# ST_LINK_V2_1.net
KiCad netlist of a schematic drawn in Altium Designer
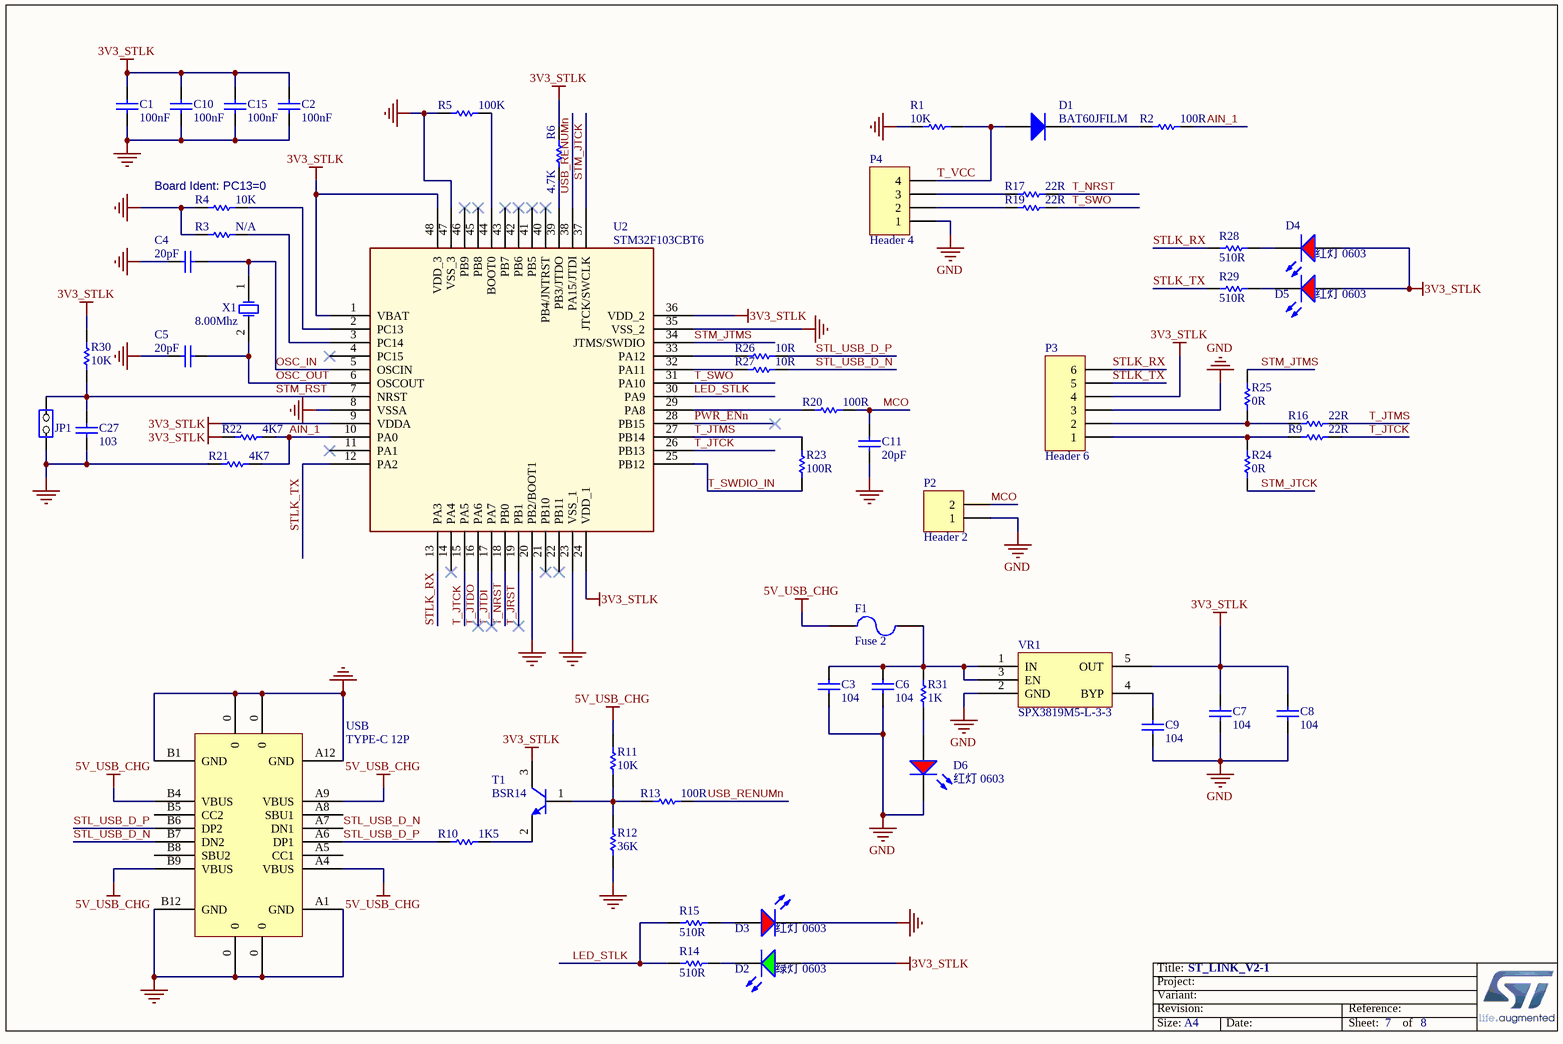
[diagram p0: ST_LINK_V2.1.SchDoc]

(export (version "E")
  (design (tool "Eeschema 10.0.6"))
  (components
    (comp (ref "C1")
      (value "100nF")
      (footprint "0603_C")
      (description "Capacitor, MLCC, 100nF, 16V, X7R, 10%, 0603, T=0,8mm")
      (fields
        (field (name "INTERNAL_PART_NUMBER") "MCD-00211")
        (field (name "MANUFACTURER_PART_NUMBER") "CC0603KRX7R7BB104")
        (field (name "PROVIDED_BY") "Subcon")
      )
      (libsource (lib "MCD_PARTS_database") (part "Capacitor"))
    )
    (comp (ref "C2")
      (value "100nF")
      (footprint "0603_C")
      (description "Capacitor, MLCC, 100nF, 16V, X7R, 10%, 0603, T=0,8mm")
      (fields
        (field (name "INTERNAL_PART_NUMBER") "MCD-00211")
        (field (name "MANUFACTURER_PART_NUMBER") "CC0603KRX7R7BB104")
        (field (name "PROVIDED_BY") "Subcon")
      )
      (libsource (lib "MCD_PARTS_database") (part "Capacitor"))
    )
    (comp (ref "C3")
      (value "104")
      (footprint "0603_C")
      (description "贴片电容")
      (libsource (lib "Miscellaneous Devices LC") (part "0603 2.7pF (2R7) 0.25pF 50V"))
    )
    (comp (ref "C4")
      (value "20pF")
      (footprint "0603_C")
      (description "Capacitor, MLCC, 10pF, 50V, NPO, 5%, 0603, T=0,8mm")
      (fields
        (field (name "INTERNAL_PART_NUMBER") "MCD-00637")
        (field (name "MANUFACTURER_PART_NUMBER") "CC0603JRNPO9BN100")
        (field (name "PROVIDED_BY") "subcon")
      )
      (libsource (lib "MCD_PARTS_database") (part "Capacitor"))
    )
    (comp (ref "C5")
      (value "20pF")
      (footprint "0603_C")
      (description "Capacitor, MLCC, 10pF, 50V, NPO, 5%, 0603, T=0,8mm")
      (fields
        (field (name "INTERNAL_PART_NUMBER") "MCD-00637")
        (field (name "MANUFACTURER_PART_NUMBER") "CC0603JRNPO9BN100")
        (field (name "PROVIDED_BY") "subcon")
      )
      (libsource (lib "MCD_PARTS_database") (part "Capacitor"))
    )
    (comp (ref "C6")
      (value "104")
      (footprint "0603_C")
      (description "贴片电容")
      (libsource (lib "Miscellaneous Devices LC") (part "0603 2.7pF (2R7) 0.25pF 50V"))
    )
    (comp (ref "C7")
      (value "104")
      (footprint "0603_C")
      (description "贴片电容")
      (libsource (lib "Miscellaneous Devices LC") (part "0603 2.7pF (2R7) 0.25pF 50V"))
    )
    (comp (ref "C8")
      (value "104")
      (footprint "0603_C")
      (description "贴片电容")
      (libsource (lib "Miscellaneous Devices LC") (part "0603 2.7pF (2R7) 0.25pF 50V"))
    )
    (comp (ref "C9")
      (value "104")
      (footprint "0603_C")
      (description "贴片电容")
      (libsource (lib "Miscellaneous Devices LC") (part "0603 2.7pF (2R7) 0.25pF 50V"))
    )
    (comp (ref "C10")
      (value "100nF")
      (footprint "0603_C")
      (description "Capacitor, MLCC, 100nF, 16V, X7R, 10%, 0603, T=0,8mm")
      (fields
        (field (name "INTERNAL_PART_NUMBER") "MCD-00211")
        (field (name "MANUFACTURER_PART_NUMBER") "CC0603KRX7R7BB104")
        (field (name "PROVIDED_BY") "Subcon")
      )
      (libsource (lib "MCD_PARTS_database") (part "Capacitor"))
    )
    (comp (ref "C11")
      (value "20pF")
      (footprint "0603_C")
      (description "Capacitor, MLCC, 20pF, 50V, NPO, 5%, 0603, T=0,8mm")
      (fields
        (field (name "INTERNAL_PART_NUMBER") "MCD-00638")
        (field (name "MANUFACTURER_PART_NUMBER") "CC0603JRNPO9BN200")
        (field (name "PROVIDED_BY") "Subcon")
      )
      (libsource (lib "MCD_PARTS_database") (part "Capacitor"))
    )
    (comp (ref "C15")
      (value "100nF")
      (footprint "0603_C")
      (description "Capacitor, MLCC, 100nF, 16V, X7R, 10%, 0603, T=0,8mm")
      (fields
        (field (name "INTERNAL_PART_NUMBER") "MCD-00211")
        (field (name "MANUFACTURER_PART_NUMBER") "CC0603KRX7R7BB104")
        (field (name "PROVIDED_BY") "Subcon")
      )
      (libsource (lib "MCD_PARTS_database") (part "Capacitor"))
    )
    (comp (ref "C27")
      (value "103")
      (footprint "0603_C")
      (description "Capacitor, MLCC, 100nF, 16V, X7R, 10%, 0603, T=0,8mm")
      (fields
        (field (name "INTERNAL_PART_NUMBER") "MCD-00211")
        (field (name "MANUFACTURER_PART_NUMBER") "CC0603KRX7R7BB104")
        (field (name "PROVIDED_BY") "Subcon")
      )
      (libsource (lib "MCD_PARTS_database") (part "Capacitor"))
    )
    (comp (ref "D1")
      (value "BAT60JFILM")
      (footprint "SOD-323")
      (fields
        (field (name "INTERNAL_PART_NUMBER") "MCD-00034")
        (field (name "MANUFACTURER") "STMICROELECTRONICS")
        (field (name "PROVIDED_BY") "Subcon")
      )
      (libsource (lib "MCD_PARTS_database") (part "BAT60JFILM"))
    )
    (comp (ref "D2")
      (value "绿灯 0603")
      (footprint "0603_LED_S1")
      (description "发光二极管")
      (libsource (lib "Miscellaneous Devices LC") (part "0603 绿灯"))
    )
    (comp (ref "D3")
      (value "红灯 0603")
      (footprint "0603_LED_S1")
      (description "发光二极管")
      (libsource (lib "Miscellaneous Devices LC") (part "0603 红灯"))
    )
    (comp (ref "D4")
      (value "红灯 0603")
      (footprint "0603_LED_S1")
      (description "发光二极管")
      (libsource (lib "Miscellaneous Devices LC") (part "0603 红灯"))
    )
    (comp (ref "D5")
      (value "红灯 0603")
      (footprint "0603_LED_S1")
      (description "发光二极管")
      (libsource (lib "Miscellaneous Devices LC") (part "0603 红灯"))
    )
    (comp (ref "D6")
      (value "红灯 0603")
      (footprint "0603_LED_S1")
      (description "发光二极管")
      (libsource (lib "Miscellaneous Devices LC") (part "0603 红灯"))
    )
    (comp (ref "F1")
      (value "Fuse 2")
      (footprint "1206_R")
      (description "Fuse")
      (fields (field (name "PUBLISHER") "Altium Limited"))
      (libsource (lib "Miscellaneous Devices") (part "Fuse 2"))
    )
    (comp (ref "JP1")
      (value "Jumper Header 2x1")
      (footprint "HDR1X2")
      (description "Header, 2x1, 2,54mm, VR, TH, Height 5.84mm/2.54mm")
      (fields
        (field (name "INTERNAL_PART_NUMBER") "MCD-00045")
        (field (name "MANUFACTURER_PART_NUMBER") "TSW-102-07-x-S")
        (field (name "PROVIDED_BY") "Subcon")
      )
      (libsource (lib "MCD_PARTS_database") (part "Jumper Header 2x1"))
    )
    (comp (ref "P2")
      (value "Header 2")
      (footprint "HDR1X2")
      (description "Header, 2-Pin")
      (fields (field (name "PUBLISHER") "Altium Limited"))
      (libsource (lib "Miscellaneous Connectors") (part "Header 2"))
    )
    (comp (ref "P3")
      (value "Header 6")
      (footprint "HDR1X6")
      (description "Header, 6-Pin")
      (fields (field (name "PUBLISHER") "Altium Limited"))
      (libsource (lib "Miscellaneous Connectors") (part "Header 6"))
    )
    (comp (ref "P4")
      (value "Header 4")
      (footprint "HDR1X4")
      (description "Header, 4-Pin")
      (fields (field (name "PUBLISHER") "Altium Limited"))
      (libsource (lib "Miscellaneous Connectors") (part "Header 4"))
    )
    (comp (ref "R1")
      (value "10K")
      (footprint "0603_R")
      (description "Resistor,10K,0603,1%,1/10W")
      (fields
        (field (name "INTERNAL_PART_NUMBER") "MCD-00220")
        (field (name "MANUFACTURER_PART_NUMBER") "RC0603FR-0710KL")
        (field (name "PROVIDED_BY") "Subcon")
      )
      (libsource (lib "MCD_PARTS_database") (part "Resistor"))
    )
    (comp (ref "R2")
      (value "100R")
      (footprint "0603_R")
      (description "Resistor,22R,0603,1%,1/10W")
      (fields
        (field (name "INTERNAL_PART_NUMBER") "MCD-00066")
        (field (name "MANUFACTURER_PART_NUMBER") "RC0603FR-0722RL")
        (field (name "PROVIDED_BY") "Subcon")
      )
      (libsource (lib "MCD_PARTS_database") (part "Resistor"))
    )
    (comp (ref "R3")
      (value "N/A")
      (footprint "0603_R")
      (description "Resistor,10K,0603,1%,1/10W")
      (fields
        (field (name "INTERNAL_PART_NUMBER") "MCD-00220")
        (field (name "MANUFACTURER_PART_NUMBER") "RC0603FR-0710KL")
        (field (name "PROVIDED_BY") "Subcon")
      )
      (libsource (lib "MCD_PARTS_database") (part "Resistor"))
    )
    (comp (ref "R4")
      (value "10K")
      (footprint "0603_R")
      (description "Resistor,10K,0603,1%,1/10W")
      (fields
        (field (name "INTERNAL_PART_NUMBER") "MCD-00220")
        (field (name "MANUFACTURER_PART_NUMBER") "RC0603FR-0710KL")
        (field (name "PROVIDED_BY") "Subcon")
      )
      (libsource (lib "MCD_PARTS_database") (part "Resistor"))
    )
    (comp (ref "R5")
      (value "100K")
      (footprint "0603_R")
      (description "Resistor,100K,0603,1%,1/10W")
      (fields
        (field (name "INTERNAL_PART_NUMBER") "MCD-00223")
        (field (name "MANUFACTURER_PART_NUMBER") "RC0603FR-07100KL")
        (field (name "PROVIDED_BY") "Subcon")
      )
      (libsource (lib "MCD_PARTS_database") (part "Resistor"))
    )
    (comp (ref "R6")
      (value "4.7K")
      (footprint "0603_R")
      (description "Resistor,330R,0603,1%,1/10W")
      (fields
        (field (name "INTERNAL_PART_NUMBER") "MCD-00197")
        (field (name "MANUFACTURER_PART_NUMBER") "RC0603FR-07330RL")
        (field (name "PROVIDED_BY") "Subcon")
      )
      (libsource (lib "MCD_PARTS_database") (part "Resistor"))
    )
    (comp (ref "R9")
      (value "22R")
      (footprint "0603_R")
      (description "Resistor,22R,0603,1%,1/10W")
      (fields
        (field (name "INTERNAL_PART_NUMBER") "MCD-00066")
        (field (name "MANUFACTURER_PART_NUMBER") "RC0603FR-0722RL")
        (field (name "PROVIDED_BY") "Subcon")
      )
      (libsource (lib "MCD_PARTS_database") (part "Resistor"))
    )
    (comp (ref "R10")
      (value "1K5")
      (footprint "0603_R")
      (description "Resistor,1K5,0603,1%,1/10W")
      (fields
        (field (name "INTERNAL_PART_NUMBER") "MCD-00217")
        (field (name "MANUFACTURER_PART_NUMBER") "RC0603FR-071K5L")
        (field (name "PROVIDED_BY") "Subcon")
      )
      (libsource (lib "MCD_PARTS_database") (part "Resistor"))
    )
    (comp (ref "R11")
      (value "10K")
      (footprint "0603_R")
      (description "Resistor,10K,0603,1%,1/10W")
      (fields
        (field (name "INTERNAL_PART_NUMBER") "MCD-00220")
        (field (name "MANUFACTURER_PART_NUMBER") "RC0603FR-0710KL")
        (field (name "PROVIDED_BY") "Subcon")
      )
      (libsource (lib "MCD_PARTS_database") (part "Resistor"))
    )
    (comp (ref "R12")
      (value "36K")
      (footprint "0603_R")
      (description "Resistor,36K,0603,1%,1/10W")
      (fields
        (field (name "INTERNAL_PART_NUMBER") "MCD-00221")
        (field (name "MANUFACTURER_PART_NUMBER") "RC0603FR-0736KL")
        (field (name "PROVIDED_BY") "Subcon")
      )
      (libsource (lib "MCD_PARTS_database") (part "Resistor"))
    )
    (comp (ref "R13")
      (value "100R")
      (footprint "0603_R")
      (description "Resistor,100R,0603,1%,1/10W")
      (fields
        (field (name "INTERNAL_PART_NUMBER") "MCD-00224")
        (field (name "MANUFACTURER_PART_NUMBER") "RC0603FR-07100RL")
        (field (name "PROVIDED_BY") "Subcon")
      )
      (libsource (lib "MCD_PARTS_database") (part "Resistor"))
    )
    (comp (ref "R14")
      (value "510R")
      (footprint "0603_R")
      (description "Resistor,330R,0603,1%,1/10W")
      (fields
        (field (name "INTERNAL_PART_NUMBER") "MCD-00197")
        (field (name "MANUFACTURER_PART_NUMBER") "RC0603FR-07330RL")
        (field (name "PROVIDED_BY") "Subcon")
      )
      (libsource (lib "MCD_PARTS_database") (part "Resistor"))
    )
    (comp (ref "R15")
      (value "510R")
      (footprint "0603_R")
      (description "Resistor,330R,0603,1%,1/10W")
      (fields
        (field (name "INTERNAL_PART_NUMBER") "MCD-00197")
        (field (name "MANUFACTURER_PART_NUMBER") "RC0603FR-07330RL")
        (field (name "PROVIDED_BY") "Subcon")
      )
      (libsource (lib "MCD_PARTS_database") (part "Resistor"))
    )
    (comp (ref "R16")
      (value "22R")
      (footprint "0603_R")
      (description "Resistor,22R,0603,1%,1/10W")
      (fields
        (field (name "INTERNAL_PART_NUMBER") "MCD-00066")
        (field (name "MANUFACTURER_PART_NUMBER") "RC0603FR-0722RL")
        (field (name "PROVIDED_BY") "Subcon")
      )
      (libsource (lib "MCD_PARTS_database") (part "Resistor"))
    )
    (comp (ref "R17")
      (value "22R")
      (footprint "0603_R")
      (description "Resistor,22R,0603,1%,1/10W")
      (fields
        (field (name "INTERNAL_PART_NUMBER") "MCD-00066")
        (field (name "MANUFACTURER_PART_NUMBER") "RC0603FR-0722RL")
        (field (name "PROVIDED_BY") "Subcon")
      )
      (libsource (lib "MCD_PARTS_database") (part "Resistor"))
    )
    (comp (ref "R19")
      (value "22R")
      (footprint "0603_R")
      (description "Resistor,22R,0603,1%,1/10W")
      (fields
        (field (name "INTERNAL_PART_NUMBER") "MCD-00066")
        (field (name "MANUFACTURER_PART_NUMBER") "RC0603FR-0722RL")
        (field (name "PROVIDED_BY") "Subcon")
      )
      (libsource (lib "MCD_PARTS_database") (part "Resistor"))
    )
    (comp (ref "R20")
      (value "100R")
      (footprint "0603_R")
      (description "Resistor,100R,0603,1%,1/10W")
      (fields
        (field (name "INTERNAL_PART_NUMBER") "MCD-00224")
        (field (name "MANUFACTURER_PART_NUMBER") "RC0603FR-07100RL")
        (field (name "PROVIDED_BY") "Subcon")
      )
      (libsource (lib "MCD_PARTS_database") (part "Resistor"))
    )
    (comp (ref "R21")
      (value "4K7")
      (footprint "0603_R")
      (description "Resistor,4K7,0603,1%,1/10W")
      (fields
        (field (name "INTERNAL_PART_NUMBER") "MCD-00219")
        (field (name "MANUFACTURER_PART_NUMBER") "RC0603FR-074K7L")
        (field (name "PROVIDED_BY") "Subcon")
      )
      (libsource (lib "MCD_PARTS_database") (part "Resistor"))
    )
    (comp (ref "R22")
      (value "4K7")
      (footprint "0603_R")
      (description "Resistor,4K7,0603,1%,1/10W")
      (fields
        (field (name "INTERNAL_PART_NUMBER") "MCD-00219")
        (field (name "MANUFACTURER_PART_NUMBER") "RC0603FR-074K7L")
        (field (name "PROVIDED_BY") "Subcon")
      )
      (libsource (lib "MCD_PARTS_database") (part "Resistor"))
    )
    (comp (ref "R23")
      (value "100R")
      (footprint "0603_R")
      (description "Resistor,100R,0603,1%,1/10W")
      (fields
        (field (name "INTERNAL_PART_NUMBER") "MCD-00224")
        (field (name "MANUFACTURER_PART_NUMBER") "RC0603FR-07100RL")
        (field (name "PROVIDED_BY") "Subcon")
      )
      (libsource (lib "MCD_PARTS_database") (part "Resistor"))
    )
    (comp (ref "R24")
      (value "0R")
      (footprint "0603_R")
      (description "Resistor,22R,0603,1%,1/10W")
      (fields
        (field (name "INTERNAL_PART_NUMBER") "MCD-00066")
        (field (name "MANUFACTURER_PART_NUMBER") "RC0603FR-0722RL")
        (field (name "PROVIDED_BY") "Subcon")
      )
      (libsource (lib "MCD_PARTS_database") (part "Resistor"))
    )
    (comp (ref "R25")
      (value "0R")
      (footprint "0603_R")
      (description "Resistor,22R,0603,1%,1/10W")
      (fields
        (field (name "INTERNAL_PART_NUMBER") "MCD-00066")
        (field (name "MANUFACTURER_PART_NUMBER") "RC0603FR-0722RL")
        (field (name "PROVIDED_BY") "Subcon")
      )
      (libsource (lib "MCD_PARTS_database") (part "Resistor"))
    )
    (comp (ref "R26")
      (value "10R")
      (footprint "0603_R")
      (description "Resistor,100R,0603,1%,1/10W")
      (fields
        (field (name "INTERNAL_PART_NUMBER") "MCD-00224")
        (field (name "MANUFACTURER_PART_NUMBER") "RC0603FR-07100RL")
        (field (name "PROVIDED_BY") "Subcon")
      )
      (libsource (lib "MCD_PARTS_database") (part "Resistor"))
    )
    (comp (ref "R27")
      (value "10R")
      (footprint "0603_R")
      (description "Resistor,100R,0603,1%,1/10W")
      (fields
        (field (name "INTERNAL_PART_NUMBER") "MCD-00224")
        (field (name "MANUFACTURER_PART_NUMBER") "RC0603FR-07100RL")
        (field (name "PROVIDED_BY") "Subcon")
      )
      (libsource (lib "MCD_PARTS_database") (part "Resistor"))
    )
    (comp (ref "R28")
      (value "510R")
      (footprint "0603_R")
      (description "Resistor,330R,0603,1%,1/10W")
      (fields
        (field (name "INTERNAL_PART_NUMBER") "MCD-00197")
        (field (name "MANUFACTURER_PART_NUMBER") "RC0603FR-07330RL")
        (field (name "PROVIDED_BY") "Subcon")
      )
      (libsource (lib "MCD_PARTS_database") (part "Resistor"))
    )
    (comp (ref "R29")
      (value "510R")
      (footprint "0603_R")
      (description "Resistor,330R,0603,1%,1/10W")
      (fields
        (field (name "INTERNAL_PART_NUMBER") "MCD-00197")
        (field (name "MANUFACTURER_PART_NUMBER") "RC0603FR-07330RL")
        (field (name "PROVIDED_BY") "Subcon")
      )
      (libsource (lib "MCD_PARTS_database") (part "Resistor"))
    )
    (comp (ref "R30")
      (value "10K")
      (footprint "0603_R")
      (description "Resistor,100K,0603,1%,1/10W")
      (fields
        (field (name "INTERNAL_PART_NUMBER") "MCD-00223")
        (field (name "MANUFACTURER_PART_NUMBER") "RC0603FR-07100KL")
        (field (name "PROVIDED_BY") "Subcon")
      )
      (libsource (lib "MCD_PARTS_database") (part "Resistor"))
    )
    (comp (ref "R31")
      (value "1K")
      (footprint "0603_R")
      (description "Resistor,330R,0603,1%,1/10W")
      (fields
        (field (name "INTERNAL_PART_NUMBER") "MCD-00197")
        (field (name "MANUFACTURER_PART_NUMBER") "RC0603FR-07330RL")
        (field (name "PROVIDED_BY") "Subcon")
      )
      (libsource (lib "MCD_PARTS_database") (part "Resistor"))
    )
    (comp (ref "T1")
      (value "9013-SOT23")
      (footprint "SOT-23(SOT-23-3)")
      (description "NPN Bipolar Transistor")
      (fields
        (field (name "INTERNAL_PART_NUMBER") "MCD-00073")
        (field (name "MANUFACTURER_PART_NUMBER") "BSR14")
        (field (name "MANUFACTURER") "NXP")
        (field (name "PROVIDED_BY") "Subcon")
      )
      (libsource (lib "MCD_PARTS_database") (part "9013-SOT23"))
    )
    (comp (ref "U2")
      (value "STM32F103CBT6")
      (footprint "LQFP-48_7x7x05P")
      (description "Medium-density performance line ARM-based 32-bit MCU with 128KB Flash")
      (fields
        (field (name "INTERNAL_PART_NUMBER") "MCD-00085")
        (field (name "MANUFACTURER") "STMICROELECTRONICS")
        (field (name "PROVIDED_BY") "Subcon")
      )
      (libsource (lib "MCD_PARTS_database") (part "STM32F103CBT6"))
    )
    (comp (ref "USB")
      (value "TYPE-C 12P")
      (footprint "TYPE-C 12P 贴片")
      (libsource (lib "PCMonitor") (part "TYPE-C 12P"))
    )
    (comp (ref "VR1")
      (value "SPX3819M5-L-3-3")
      (footprint "SOT-23-5")
      (description "LDO")
      (libsource (lib "My_Schlib") (part "SPX3819M5-L-3-3"))
    )
    (comp (ref "X1")
      (value "8.00Mhz")
      (footprint "SMD-5032_2P")
      (description "Crystal 8Mhz, 8pF, -+50PPM, SMD")
      (fields
        (field (name "INTERNAL_PART_NUMBER") "MCD-00092")
        (field (name "MANUFACTURER_PART_NUMBER") "NX3225GD 8MHz EXS00A-CG04874")
        (field (name "PROVIDED_BY") "STM")
      )
      (libsource (lib "MCD_PARTS_database") (part "XTAL_8M_NX3225GD"))
    )
  )
  (nets
    (net (code "1") (name "/AIN_1") (class "Default")
      (node (ref "R2") (pin "2") (pinfunction "2_2") (pintype "passive"))
      (node (ref "R21") (pin "2") (pinfunction "2_2") (pintype "passive"))
      (node (ref "R22") (pin "2") (pinfunction "2_2") (pintype "passive"))
      (node (ref "U2") (pin "10") (pinfunction "PA0_10") (pintype "passive"))
    )
    (net (code "2") (name "/LED_STLK") (class "Default")
      (node (ref "R14") (pin "1") (pinfunction "1_1") (pintype "passive"))
      (node (ref "R15") (pin "1") (pinfunction "1_1") (pintype "passive"))
      (node (ref "U2") (pin "30") (pinfunction "PA9_30") (pintype "passive"))
    )
    (net (code "3") (name "/MCO") (class "Default")
      (node (ref "C11") (pin "1") (pinfunction "1_1") (pintype "passive"))
      (node (ref "P2") (pin "2") (pinfunction "2_2") (pintype "passive"))
      (node (ref "R20") (pin "2") (pinfunction "2_2") (pintype "passive"))
    )
    (net (code "4") (name "/OSC_IN") (class "Default")
      (node (ref "C4") (pin "2") (pinfunction "2_2") (pintype "passive"))
      (node (ref "U2") (pin "5") (pinfunction "OSCIN_5") (pintype "passive"))
      (node (ref "X1") (pin "1") (pinfunction "OSC1_1") (pintype "passive"))
    )
    (net (code "5") (name "/OSC_OUT") (class "Default")
      (node (ref "C5") (pin "2") (pinfunction "2_2") (pintype "passive"))
      (node (ref "U2") (pin "6") (pinfunction "OSCOUT_6") (pintype "passive"))
      (node (ref "X1") (pin "2") (pinfunction "OSC2_2") (pintype "passive"))
    )
    (net (code "6") (name "/PWR_ENn") (class "Default")
      (node (ref "U2") (pin "28") (pinfunction "PB15_28") (pintype "passive+no_connect"))
    )
    (net (code "7") (name "/STLK_RX") (class "Default")
      (node (ref "P3") (pin "6") (pinfunction "6_6") (pintype "passive"))
      (node (ref "R28") (pin "1") (pinfunction "1_1") (pintype "passive"))
      (node (ref "U2") (pin "13") (pinfunction "PA3_13") (pintype "passive"))
    )
    (net (code "8") (name "/STLK_TX") (class "Default")
      (node (ref "P3") (pin "5") (pinfunction "5_5") (pintype "passive"))
      (node (ref "R29") (pin "1") (pinfunction "1_1") (pintype "passive"))
      (node (ref "U2") (pin "12") (pinfunction "PA2_12") (pintype "passive"))
    )
    (net (code "9") (name "/STL_USB_D_N") (class "Default")
      (node (ref "R27") (pin "2") (pinfunction "2_2") (pintype "passive"))
      (node (ref "USB") (pin "A7") (pinfunction "DN1_A7") (pintype "passive"))
      (node (ref "USB") (pin "B7") (pinfunction "DN2_B7") (pintype "passive"))
    )
    (net (code "10") (name "/STL_USB_D_P") (class "Default")
      (node (ref "R10") (pin "1") (pinfunction "1_1") (pintype "passive"))
      (node (ref "R26") (pin "2") (pinfunction "2_2") (pintype "passive"))
      (node (ref "USB") (pin "A6") (pinfunction "DP1_A6") (pintype "passive"))
      (node (ref "USB") (pin "B6") (pinfunction "DP2_B6") (pintype "passive"))
    )
    (net (code "11") (name "/STM_JTCK") (class "Default")
      (node (ref "R24") (pin "1") (pinfunction "1_1") (pintype "passive"))
      (node (ref "U2") (pin "37") (pinfunction "JTCK/SWCLK_37") (pintype "passive"))
    )
    (net (code "12") (name "/STM_JTMS") (class "Default")
      (node (ref "R25") (pin "2") (pinfunction "2_2") (pintype "passive"))
      (node (ref "U2") (pin "34") (pinfunction "JTMS/SWDIO_34") (pintype "passive"))
    )
    (net (code "13") (name "/STM_RST") (class "Default")
      (node (ref "C27") (pin "1") (pinfunction "1_1") (pintype "passive"))
      (node (ref "JP1") (pin "1") (pinfunction "COMMON_1") (pintype "passive"))
      (node (ref "R30") (pin "1") (pinfunction "1_1") (pintype "passive"))
      (node (ref "U2") (pin "7") (pinfunction "NRST_7") (pintype "passive"))
    )
    (net (code "14") (name "/T_JRST") (class "Default")
      (node (ref "U2") (pin "19") (pinfunction "PB1_19") (pintype "passive+no_connect"))
    )
    (net (code "15") (name "/T_JTCK") (class "Default")
      (node (ref "R9") (pin "2") (pinfunction "2_2") (pintype "passive"))
      (node (ref "U2") (pin "15") (pinfunction "PA5_15") (pintype "passive"))
      (node (ref "U2") (pin "26") (pinfunction "PB13_26") (pintype "passive"))
    )
    (net (code "16") (name "/T_JTDI") (class "Default")
      (node (ref "U2") (pin "17") (pinfunction "PA7_17") (pintype "passive+no_connect"))
    )
    (net (code "17") (name "/T_JTDO") (class "Default")
      (node (ref "U2") (pin "16") (pinfunction "PA6_16") (pintype "passive+no_connect"))
    )
    (net (code "18") (name "/T_JTMS") (class "Default")
      (node (ref "R16") (pin "2") (pinfunction "2_2") (pintype "passive"))
      (node (ref "R23") (pin "2") (pinfunction "2_2") (pintype "passive"))
      (node (ref "U2") (pin "27") (pinfunction "PB14_27") (pintype "passive"))
    )
    (net (code "19") (name "/T_NRST") (class "Default")
      (node (ref "R17") (pin "2") (pinfunction "2_2") (pintype "passive"))
      (node (ref "U2") (pin "18") (pinfunction "PB0_18") (pintype "passive"))
    )
    (net (code "20") (name "/T_SWDIO_IN") (class "Default")
      (node (ref "R23") (pin "1") (pinfunction "1_1") (pintype "passive"))
      (node (ref "U2") (pin "25") (pinfunction "PB12_25") (pintype "passive"))
    )
    (net (code "21") (name "/T_SWO") (class "Default")
      (node (ref "R19") (pin "2") (pinfunction "2_2") (pintype "passive"))
      (node (ref "U2") (pin "31") (pinfunction "PA10_31") (pintype "passive"))
    )
    (net (code "22") (name "/T_VCC") (class "Default")
      (node (ref "D1") (pin "1") (pinfunction "A_1") (pintype "passive"))
      (node (ref "P4") (pin "4") (pinfunction "4_4") (pintype "passive"))
      (node (ref "R1") (pin "1") (pinfunction "1_1") (pintype "passive"))
    )
    (net (code "23") (name "/USB_RENUMn") (class "Default")
      (node (ref "R13") (pin "2") (pinfunction "2_2") (pintype "passive"))
      (node (ref "U2") (pin "38") (pinfunction "PA15/JTDI_38") (pintype "passive"))
    )
    (net (code "24") (name "3V3_STLK") (class "Default")
      (node (ref "C1") (pin "2") (pinfunction "2_2") (pintype "passive"))
      (node (ref "C10") (pin "2") (pinfunction "2_2") (pintype "passive"))
      (node (ref "C15") (pin "2") (pinfunction "2_2") (pintype "passive"))
      (node (ref "C2") (pin "2") (pinfunction "2_2") (pintype "passive"))
      (node (ref "C7") (pin "2") (pinfunction "2_2") (pintype "passive"))
      (node (ref "C8") (pin "2") (pinfunction "2_2") (pintype "passive"))
      (node (ref "D2") (pin "A") (pinfunction "A_A") (pintype "passive"))
      (node (ref "D4") (pin "A") (pinfunction "A_A") (pintype "passive"))
      (node (ref "D5") (pin "A") (pinfunction "A_A") (pintype "passive"))
      (node (ref "P3") (pin "4") (pinfunction "4_4") (pintype "passive"))
      (node (ref "R22") (pin "1") (pinfunction "1_1") (pintype "passive"))
      (node (ref "R30") (pin "2") (pinfunction "2_2") (pintype "passive"))
      (node (ref "R6") (pin "2") (pinfunction "2_2") (pintype "passive"))
      (node (ref "T1") (pin "3") (pinfunction "C_3") (pintype "passive"))
      (node (ref "U2") (pin "1") (pinfunction "VBAT_1") (pintype "passive"))
      (node (ref "U2") (pin "24") (pinfunction "VDD_1_24") (pintype "passive"))
      (node (ref "U2") (pin "36") (pinfunction "VDD_2_36") (pintype "passive"))
      (node (ref "U2") (pin "48") (pinfunction "VDD_3_48") (pintype "passive"))
      (node (ref "U2") (pin "9") (pinfunction "VDDA_9") (pintype "passive"))
      (node (ref "VR1") (pin "5") (pinfunction "OUT_5") (pintype "passive"))
    )
    (net (code "25") (name "5V_USB_CHG") (class "Default")
      (node (ref "F1") (pin "1") (pinfunction "1_1") (pintype "passive"))
      (node (ref "R11") (pin "2") (pinfunction "2_2") (pintype "passive"))
      (node (ref "USB") (pin "A4") (pinfunction "VBUS_A4") (pintype "passive"))
      (node (ref "USB") (pin "A9") (pinfunction "VBUS_A9") (pintype "passive"))
      (node (ref "USB") (pin "B4") (pinfunction "VBUS_B4") (pintype "passive"))
      (node (ref "USB") (pin "B9") (pinfunction "VBUS_B9") (pintype "passive"))
    )
    (net (code "26") (name "GND") (class "Default")
      (node (ref "C1") (pin "1") (pinfunction "1_1") (pintype "passive"))
      (node (ref "C10") (pin "1") (pinfunction "1_1") (pintype "passive"))
      (node (ref "C11") (pin "2") (pinfunction "2_2") (pintype "passive"))
      (node (ref "C15") (pin "1") (pinfunction "1_1") (pintype "passive"))
      (node (ref "C2") (pin "1") (pinfunction "1_1") (pintype "passive"))
      (node (ref "C27") (pin "2") (pinfunction "2_2") (pintype "passive"))
      (node (ref "C3") (pin "1") (pinfunction "1_1") (pintype "passive"))
      (node (ref "C4") (pin "1") (pinfunction "1_1") (pintype "passive"))
      (node (ref "C5") (pin "1") (pinfunction "1_1") (pintype "passive"))
      (node (ref "C6") (pin "1") (pinfunction "1_1") (pintype "passive"))
      (node (ref "C7") (pin "1") (pinfunction "1_1") (pintype "passive"))
      (node (ref "C8") (pin "1") (pinfunction "1_1") (pintype "passive"))
      (node (ref "C9") (pin "1") (pinfunction "1_1") (pintype "passive"))
      (node (ref "D3") (pin "K") (pinfunction "K_K") (pintype "passive"))
      (node (ref "D6") (pin "K") (pinfunction "K_K") (pintype "passive"))
      (node (ref "JP1") (pin "2") (pinfunction "NO_2") (pintype "passive"))
      (node (ref "P2") (pin "1") (pinfunction "1_1") (pintype "passive"))
      (node (ref "P3") (pin "3") (pinfunction "3_3") (pintype "passive"))
      (node (ref "P4") (pin "1") (pinfunction "1_1") (pintype "passive"))
      (node (ref "R1") (pin "2") (pinfunction "2_2") (pintype "passive"))
      (node (ref "R12") (pin "1") (pinfunction "1_1") (pintype "passive"))
      (node (ref "R21") (pin "1") (pinfunction "1_1") (pintype "passive"))
      (node (ref "R3") (pin "1") (pinfunction "1_1") (pintype "passive"))
      (node (ref "R4") (pin "1") (pinfunction "1_1") (pintype "passive"))
      (node (ref "R5") (pin "1") (pinfunction "1_1") (pintype "passive"))
      (node (ref "U2") (pin "20") (pinfunction "PB2/BOOT1_20") (pintype "passive"))
      (node (ref "U2") (pin "23") (pinfunction "VSS_1_23") (pintype "passive"))
      (node (ref "U2") (pin "35") (pinfunction "VSS_2_35") (pintype "passive"))
      (node (ref "U2") (pin "47") (pinfunction "VSS_3_47") (pintype "passive"))
      (node (ref "U2") (pin "8") (pinfunction "VSSA_8") (pintype "passive"))
      (node (ref "USB") (pin "0") (pinfunction "0_0") (pintype "passive"))
      (node (ref "USB") (pin "A1") (pinfunction "GND_A1") (pintype "passive"))
      (node (ref "USB") (pin "A12") (pinfunction "GND_A12") (pintype "passive"))
      (node (ref "USB") (pin "B1") (pinfunction "GND_B1") (pintype "passive"))
      (node (ref "USB") (pin "B12") (pinfunction "GND_B12") (pintype "passive"))
      (node (ref "VR1") (pin "2") (pinfunction "GND_2") (pintype "passive"))
    )
    (net (code "27") (name "Net-(D1-K)") (class "Default")
      (node (ref "D1") (pin "2") (pinfunction "K_2") (pintype "passive"))
      (node (ref "R2") (pin "1") (pinfunction "1_1") (pintype "passive"))
    )
    (net (code "28") (name "Net-(D2-PadK)") (class "Default")
      (node (ref "D2") (pin "K") (pinfunction "K_K") (pintype "passive"))
      (node (ref "R14") (pin "2") (pinfunction "2_2") (pintype "passive"))
    )
    (net (code "29") (name "Net-(D3-PadA)") (class "Default")
      (node (ref "D3") (pin "A") (pinfunction "A_A") (pintype "passive"))
      (node (ref "R15") (pin "2") (pinfunction "2_2") (pintype "passive"))
    )
    (net (code "30") (name "Net-(D4-PadK)") (class "Default")
      (node (ref "D4") (pin "K") (pinfunction "K_K") (pintype "passive"))
      (node (ref "R28") (pin "2") (pinfunction "2_2") (pintype "passive"))
    )
    (net (code "31") (name "Net-(D5-PadK)") (class "Default")
      (node (ref "D5") (pin "K") (pinfunction "K_K") (pintype "passive"))
      (node (ref "R29") (pin "2") (pinfunction "2_2") (pintype "passive"))
    )
    (net (code "32") (name "Net-(D6-PadA)") (class "Default")
      (node (ref "D6") (pin "A") (pinfunction "A_A") (pintype "passive"))
      (node (ref "R31") (pin "2") (pinfunction "2_2") (pintype "passive"))
    )
    (net (code "33") (name "Net-(P3-Pad1)") (class "Default")
      (node (ref "P3") (pin "1") (pinfunction "1_1") (pintype "passive"))
      (node (ref "R24") (pin "2") (pinfunction "2_2") (pintype "passive"))
      (node (ref "R9") (pin "1") (pinfunction "1_1") (pintype "passive"))
    )
    (net (code "34") (name "Net-(P3-Pad2)") (class "Default")
      (node (ref "P3") (pin "2") (pinfunction "2_2") (pintype "passive"))
      (node (ref "R16") (pin "1") (pinfunction "1_1") (pintype "passive"))
      (node (ref "R25") (pin "1") (pinfunction "1_1") (pintype "passive"))
    )
    (net (code "35") (name "Net-(P4-Pad2)") (class "Default")
      (node (ref "P4") (pin "2") (pinfunction "2_2") (pintype "passive"))
      (node (ref "R19") (pin "1") (pinfunction "1_1") (pintype "passive"))
    )
    (net (code "36") (name "Net-(P4-Pad3)") (class "Default")
      (node (ref "P4") (pin "3") (pinfunction "3_3") (pintype "passive"))
      (node (ref "R17") (pin "1") (pinfunction "1_1") (pintype "passive"))
    )
    (net (code "37") (name "Net-(T1-B)") (class "Default")
      (node (ref "R11") (pin "1") (pinfunction "1_1") (pintype "passive"))
      (node (ref "R12") (pin "2") (pinfunction "2_2") (pintype "passive"))
      (node (ref "R13") (pin "1") (pinfunction "1_1") (pintype "passive"))
      (node (ref "T1") (pin "1") (pinfunction "B_1") (pintype "passive"))
    )
    (net (code "38") (name "Net-(T1-E)") (class "Default")
      (node (ref "R10") (pin "2") (pinfunction "2_2") (pintype "passive"))
      (node (ref "T1") (pin "2") (pinfunction "E_2") (pintype "passive"))
    )
    (net (code "39") (name "Net-(U2-BOOT0)") (class "Default")
      (node (ref "R5") (pin "2") (pinfunction "2_2") (pintype "passive"))
      (node (ref "U2") (pin "44") (pinfunction "BOOT0_44") (pintype "passive"))
    )
    (net (code "40") (name "Net-(U2-PA8)") (class "Default")
      (node (ref "R20") (pin "1") (pinfunction "1_1") (pintype "passive"))
      (node (ref "U2") (pin "29") (pinfunction "PA8_29") (pintype "passive"))
    )
    (net (code "41") (name "Net-(U2-PA11)") (class "Default")
      (node (ref "R27") (pin "1") (pinfunction "1_1") (pintype "passive"))
      (node (ref "U2") (pin "32") (pinfunction "PA11_32") (pintype "passive"))
    )
    (net (code "42") (name "Net-(U2-PA12)") (class "Default")
      (node (ref "R26") (pin "1") (pinfunction "1_1") (pintype "passive"))
      (node (ref "U2") (pin "33") (pinfunction "PA12_33") (pintype "passive"))
    )
    (net (code "43") (name "Net-(U2-PB3{slash}JTDO)") (class "Default")
      (node (ref "R6") (pin "1") (pinfunction "1_1") (pintype "passive"))
      (node (ref "U2") (pin "39") (pinfunction "PB3/JTDO_39") (pintype "passive"))
    )
    (net (code "44") (name "Net-(U2-PC13)") (class "Default")
      (node (ref "R4") (pin "2") (pinfunction "2_2") (pintype "passive"))
      (node (ref "U2") (pin "2") (pinfunction "PC13_2") (pintype "passive"))
    )
    (net (code "45") (name "Net-(U2-PC14)") (class "Default")
      (node (ref "R3") (pin "2") (pinfunction "2_2") (pintype "passive"))
      (node (ref "U2") (pin "3") (pinfunction "PC14_3") (pintype "passive"))
    )
    (net (code "46") (name "Net-(VR1-BYP)") (class "Default")
      (node (ref "C9") (pin "2") (pinfunction "2_2") (pintype "passive"))
      (node (ref "VR1") (pin "4") (pinfunction "BYP_4") (pintype "passive"))
    )
    (net (code "47") (name "Net-(VR1-EN)") (class "Default")
      (node (ref "C3") (pin "2") (pinfunction "2_2") (pintype "passive"))
      (node (ref "C6") (pin "2") (pinfunction "2_2") (pintype "passive"))
      (node (ref "F1") (pin "2") (pinfunction "2_2") (pintype "passive"))
      (node (ref "R31") (pin "1") (pinfunction "1_1") (pintype "passive"))
      (node (ref "VR1") (pin "1") (pinfunction "IN_1") (pintype "passive"))
      (node (ref "VR1") (pin "3") (pinfunction "EN_3") (pintype "passive"))
    )
    (net (code "48") (name "unconnected-(U2-PA1-Pad11)") (class "Default")
      (node (ref "U2") (pin "11") (pinfunction "PA1_11") (pintype "passive+no_connect"))
    )
    (net (code "49") (name "unconnected-(U2-PA4-Pad14)") (class "Default")
      (node (ref "U2") (pin "14") (pinfunction "PA4_14") (pintype "passive+no_connect"))
    )
    (net (code "50") (name "unconnected-(U2-PB4{slash}JNTRST-Pad40)") (class "Default")
      (node (ref "U2") (pin "40") (pinfunction "PB4/JNTRST_40") (pintype "passive+no_connect"))
    )
    (net (code "51") (name "unconnected-(U2-PB5-Pad41)") (class "Default")
      (node (ref "U2") (pin "41") (pinfunction "PB5_41") (pintype "passive+no_connect"))
    )
    (net (code "52") (name "unconnected-(U2-PB6-Pad42)") (class "Default")
      (node (ref "U2") (pin "42") (pinfunction "PB6_42") (pintype "passive+no_connect"))
    )
    (net (code "53") (name "unconnected-(U2-PB7-Pad43)") (class "Default")
      (node (ref "U2") (pin "43") (pinfunction "PB7_43") (pintype "passive+no_connect"))
    )
    (net (code "54") (name "unconnected-(U2-PB8-Pad45)") (class "Default")
      (node (ref "U2") (pin "45") (pinfunction "PB8_45") (pintype "passive+no_connect"))
    )
    (net (code "55") (name "unconnected-(U2-PB9-Pad46)") (class "Default")
      (node (ref "U2") (pin "46") (pinfunction "PB9_46") (pintype "passive+no_connect"))
    )
    (net (code "56") (name "unconnected-(U2-PB10-Pad21)") (class "Default")
      (node (ref "U2") (pin "21") (pinfunction "PB10_21") (pintype "passive+no_connect"))
    )
    (net (code "57") (name "unconnected-(U2-PB11-Pad22)") (class "Default")
      (node (ref "U2") (pin "22") (pinfunction "PB11_22") (pintype "passive+no_connect"))
    )
    (net (code "58") (name "unconnected-(U2-PC15-Pad4)") (class "Default")
      (node (ref "U2") (pin "4") (pinfunction "PC15_4") (pintype "passive+no_connect"))
    )
    (net (code "59") (name "unconnected-(USB-CC1-PadA5)") (class "Default")
      (node (ref "USB") (pin "A5") (pinfunction "CC1_A5") (pintype "passive"))
    )
    (net (code "60") (name "unconnected-(USB-CC2-PadB5)") (class "Default")
      (node (ref "USB") (pin "B5") (pinfunction "CC2_B5") (pintype "passive"))
    )
    (net (code "61") (name "unconnected-(USB-SBU1-PadA8)") (class "Default")
      (node (ref "USB") (pin "A8") (pinfunction "SBU1_A8") (pintype "passive"))
    )
    (net (code "62") (name "unconnected-(USB-SBU2-PadB8)") (class "Default")
      (node (ref "USB") (pin "B8") (pinfunction "SBU2_B8") (pintype "passive"))
    )
  )
)
